# stk200.net
KiCad netlist of a schematic drawn in EAGLE
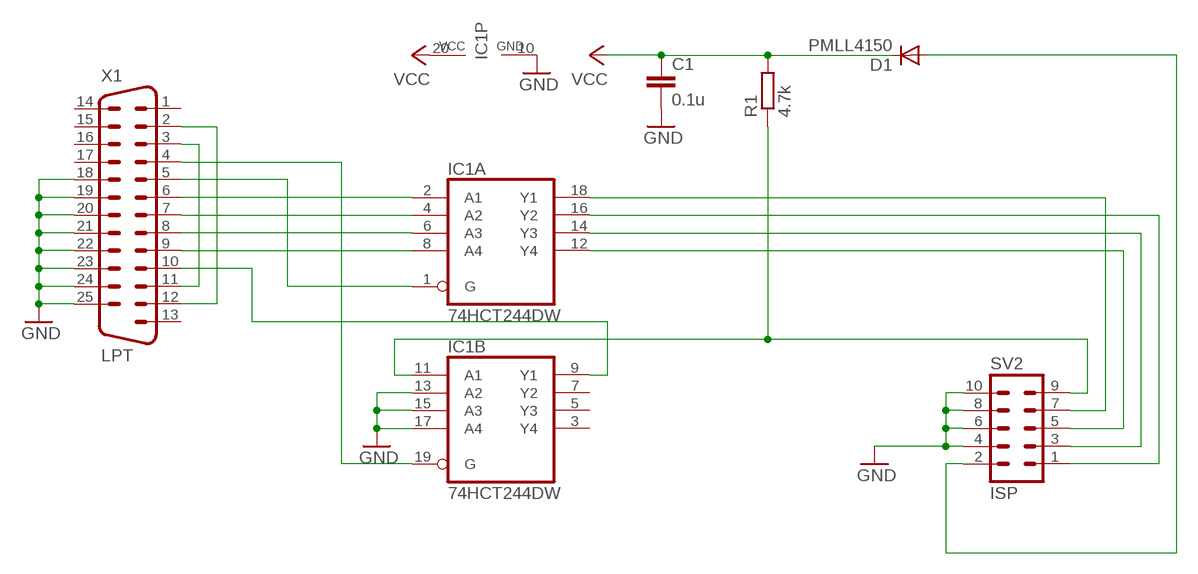
[diagram p0: schematic, sheet 1]

(export (version "E")
  (design (tool "Eeschema 10.0.6"))
  (components
    (comp (ref "C1")
      (value "0.1u")
      (footprint "eagle-import:C0805")
      (libsource (lib "eagle-import") (part "C-EUC0805"))
    )
    (comp (ref "D1")
      (value "PMLL4150")
      (footprint "eagle-import:SOD80C")
      (libsource (lib "eagle-import") (part "PMLL4150"))
    )
    (comp (ref "IC1")
      (value "74HCT244DW")
      (footprint "eagle-import:SO20W")
      (libsource (lib "eagle-import") (part "74244DWHCT"))
    )
    (comp (ref "R1")
      (value "4.7k")
      (footprint "eagle-import:R0805")
      (libsource (lib "eagle-import") (part "R-EU_R0805"))
    )
    (comp (ref "SV2")
      (value "ISP")
      (footprint "eagle-import:MA05-2")
      (libsource (lib "eagle-import") (part "MA05-2"))
    )
    (comp (ref "X1")
      (value "LPT")
      (footprint "eagle-import:M25D")
      (libsource (lib "eagle-import") (part "M25D"))
    )
  )
  (nets
    (net (code "1") (name "GND") (class "Default")
      (node (ref "C1") (pin "2") (pinfunction "2_2") (pintype "passive"))
      (node (ref "IC1") (pin "10") (pinfunction "GND_10") (pintype "power_in"))
      (node (ref "IC1") (pin "13") (pinfunction "A2_13") (pintype "input"))
      (node (ref "IC1") (pin "15") (pinfunction "A3_15") (pintype "input"))
      (node (ref "IC1") (pin "17") (pinfunction "A4_17") (pintype "input"))
      (node (ref "SV2") (pin "10") (pinfunction "10_10") (pintype "passive"))
      (node (ref "SV2") (pin "4") (pinfunction "4_4") (pintype "passive"))
      (node (ref "SV2") (pin "6") (pinfunction "6_6") (pintype "passive"))
      (node (ref "SV2") (pin "8") (pinfunction "8_8") (pintype "passive"))
      (node (ref "X1") (pin "18") (pinfunction "18_18") (pintype "passive"))
      (node (ref "X1") (pin "19") (pinfunction "19_19") (pintype "passive"))
      (node (ref "X1") (pin "20") (pinfunction "20_20") (pintype "passive"))
      (node (ref "X1") (pin "21") (pinfunction "21_21") (pintype "passive"))
      (node (ref "X1") (pin "22") (pinfunction "22_22") (pintype "passive"))
      (node (ref "X1") (pin "23") (pinfunction "23_23") (pintype "passive"))
      (node (ref "X1") (pin "24") (pinfunction "24_24") (pintype "passive"))
      (node (ref "X1") (pin "25") (pinfunction "25_25") (pintype "passive"))
    )
    (net (code "2") (name "Net-(D1-PadA)") (class "Default")
      (node (ref "D1") (pin "A") (pinfunction "A_A") (pintype "passive"))
      (node (ref "SV2") (pin "2") (pinfunction "2_2") (pintype "passive"))
    )
    (net (code "3") (name "Net-(IC1A-A1)") (class "Default")
      (node (ref "IC1") (pin "2") (pinfunction "A1_2") (pintype "input"))
      (node (ref "X1") (pin "6") (pinfunction "6_6") (pintype "passive"))
    )
    (net (code "4") (name "Net-(IC1A-A2)") (class "Default")
      (node (ref "IC1") (pin "4") (pinfunction "A2_4") (pintype "input"))
      (node (ref "X1") (pin "7") (pinfunction "7_7") (pintype "passive"))
    )
    (net (code "5") (name "Net-(IC1A-A3)") (class "Default")
      (node (ref "IC1") (pin "6") (pinfunction "A3_6") (pintype "input"))
      (node (ref "X1") (pin "8") (pinfunction "8_8") (pintype "passive"))
    )
    (net (code "6") (name "Net-(IC1A-A4)") (class "Default")
      (node (ref "IC1") (pin "8") (pinfunction "A4_8") (pintype "input"))
      (node (ref "X1") (pin "9") (pinfunction "9_9") (pintype "passive"))
    )
    (net (code "7") (name "Net-(IC1A-G)") (class "Default")
      (node (ref "IC1") (pin "1") (pinfunction "G_1") (pintype "input"))
      (node (ref "X1") (pin "5") (pinfunction "5_5") (pintype "passive"))
    )
    (net (code "8") (name "Net-(IC1A-Y1)") (class "Default")
      (node (ref "IC1") (pin "18") (pinfunction "Y1_18") (pintype "tri_state"))
      (node (ref "SV2") (pin "7") (pinfunction "7_7") (pintype "passive"))
    )
    (net (code "9") (name "Net-(IC1A-Y2)") (class "Default")
      (node (ref "IC1") (pin "16") (pinfunction "Y2_16") (pintype "tri_state"))
      (node (ref "SV2") (pin "1") (pinfunction "1_1") (pintype "passive"))
    )
    (net (code "10") (name "Net-(IC1A-Y3)") (class "Default")
      (node (ref "IC1") (pin "14") (pinfunction "Y3_14") (pintype "tri_state"))
      (node (ref "SV2") (pin "3") (pinfunction "3_3") (pintype "passive"))
    )
    (net (code "11") (name "Net-(IC1A-Y4)") (class "Default")
      (node (ref "IC1") (pin "12") (pinfunction "Y4_12") (pintype "tri_state"))
      (node (ref "SV2") (pin "5") (pinfunction "5_5") (pintype "passive"))
    )
    (net (code "12") (name "Net-(IC1B-A1)") (class "Default")
      (node (ref "IC1") (pin "11") (pinfunction "A1_11") (pintype "input"))
      (node (ref "R1") (pin "1") (pinfunction "1_1") (pintype "passive"))
      (node (ref "SV2") (pin "9") (pinfunction "9_9") (pintype "passive"))
    )
    (net (code "13") (name "Net-(IC1B-G)") (class "Default")
      (node (ref "IC1") (pin "19") (pinfunction "G_19") (pintype "input"))
      (node (ref "X1") (pin "4") (pinfunction "4_4") (pintype "passive"))
    )
    (net (code "14") (name "Net-(IC1B-Y1)") (class "Default")
      (node (ref "IC1") (pin "9") (pinfunction "Y1_9") (pintype "tri_state"))
      (node (ref "X1") (pin "10") (pinfunction "10_10") (pintype "passive"))
    )
    (net (code "15") (name "Net-(X1-Pad11)") (class "Default")
      (node (ref "X1") (pin "11") (pinfunction "11_11") (pintype "passive"))
      (node (ref "X1") (pin "3") (pinfunction "3_3") (pintype "passive"))
    )
    (net (code "16") (name "Net-(X1-Pad12)") (class "Default")
      (node (ref "X1") (pin "12") (pinfunction "12_12") (pintype "passive"))
      (node (ref "X1") (pin "2") (pinfunction "2_2") (pintype "passive"))
    )
    (net (code "17") (name "VCC") (class "Default")
      (node (ref "C1") (pin "1") (pinfunction "1_1") (pintype "passive"))
      (node (ref "D1") (pin "C") (pinfunction "C_C") (pintype "passive"))
      (node (ref "IC1") (pin "20") (pinfunction "VCC_20") (pintype "power_in"))
      (node (ref "R1") (pin "2") (pinfunction "2_2") (pintype "passive"))
    )
    (net (code "18") (name "unconnected-(IC1B-Y2-Pad7)") (class "Default")
      (node (ref "IC1") (pin "7") (pinfunction "Y2_7") (pintype "tri_state"))
    )
    (net (code "19") (name "unconnected-(IC1B-Y3-Pad5)") (class "Default")
      (node (ref "IC1") (pin "5") (pinfunction "Y3_5") (pintype "tri_state"))
    )
    (net (code "20") (name "unconnected-(IC1B-Y4-Pad3)") (class "Default")
      (node (ref "IC1") (pin "3") (pinfunction "Y4_3") (pintype "tri_state"))
    )
    (net (code "21") (name "unconnected-(X1-Pad1)") (class "Default")
      (node (ref "X1") (pin "1") (pinfunction "1_1") (pintype "passive"))
    )
    (net (code "22") (name "unconnected-(X1-Pad13)") (class "Default")
      (node (ref "X1") (pin "13") (pinfunction "13_13") (pintype "passive"))
    )
    (net (code "23") (name "unconnected-(X1-Pad14)") (class "Default")
      (node (ref "X1") (pin "14") (pinfunction "14_14") (pintype "passive"))
    )
    (net (code "24") (name "unconnected-(X1-Pad15)") (class "Default")
      (node (ref "X1") (pin "15") (pinfunction "15_15") (pintype "passive"))
    )
    (net (code "25") (name "unconnected-(X1-Pad16)") (class "Default")
      (node (ref "X1") (pin "16") (pinfunction "16_16") (pintype "passive"))
    )
    (net (code "26") (name "unconnected-(X1-Pad17)") (class "Default")
      (node (ref "X1") (pin "17") (pinfunction "17_17") (pintype "passive"))
    )
  )
)
